# MicrocontrollerCircuit.net
KiCad netlist of a schematic drawn in EAGLE
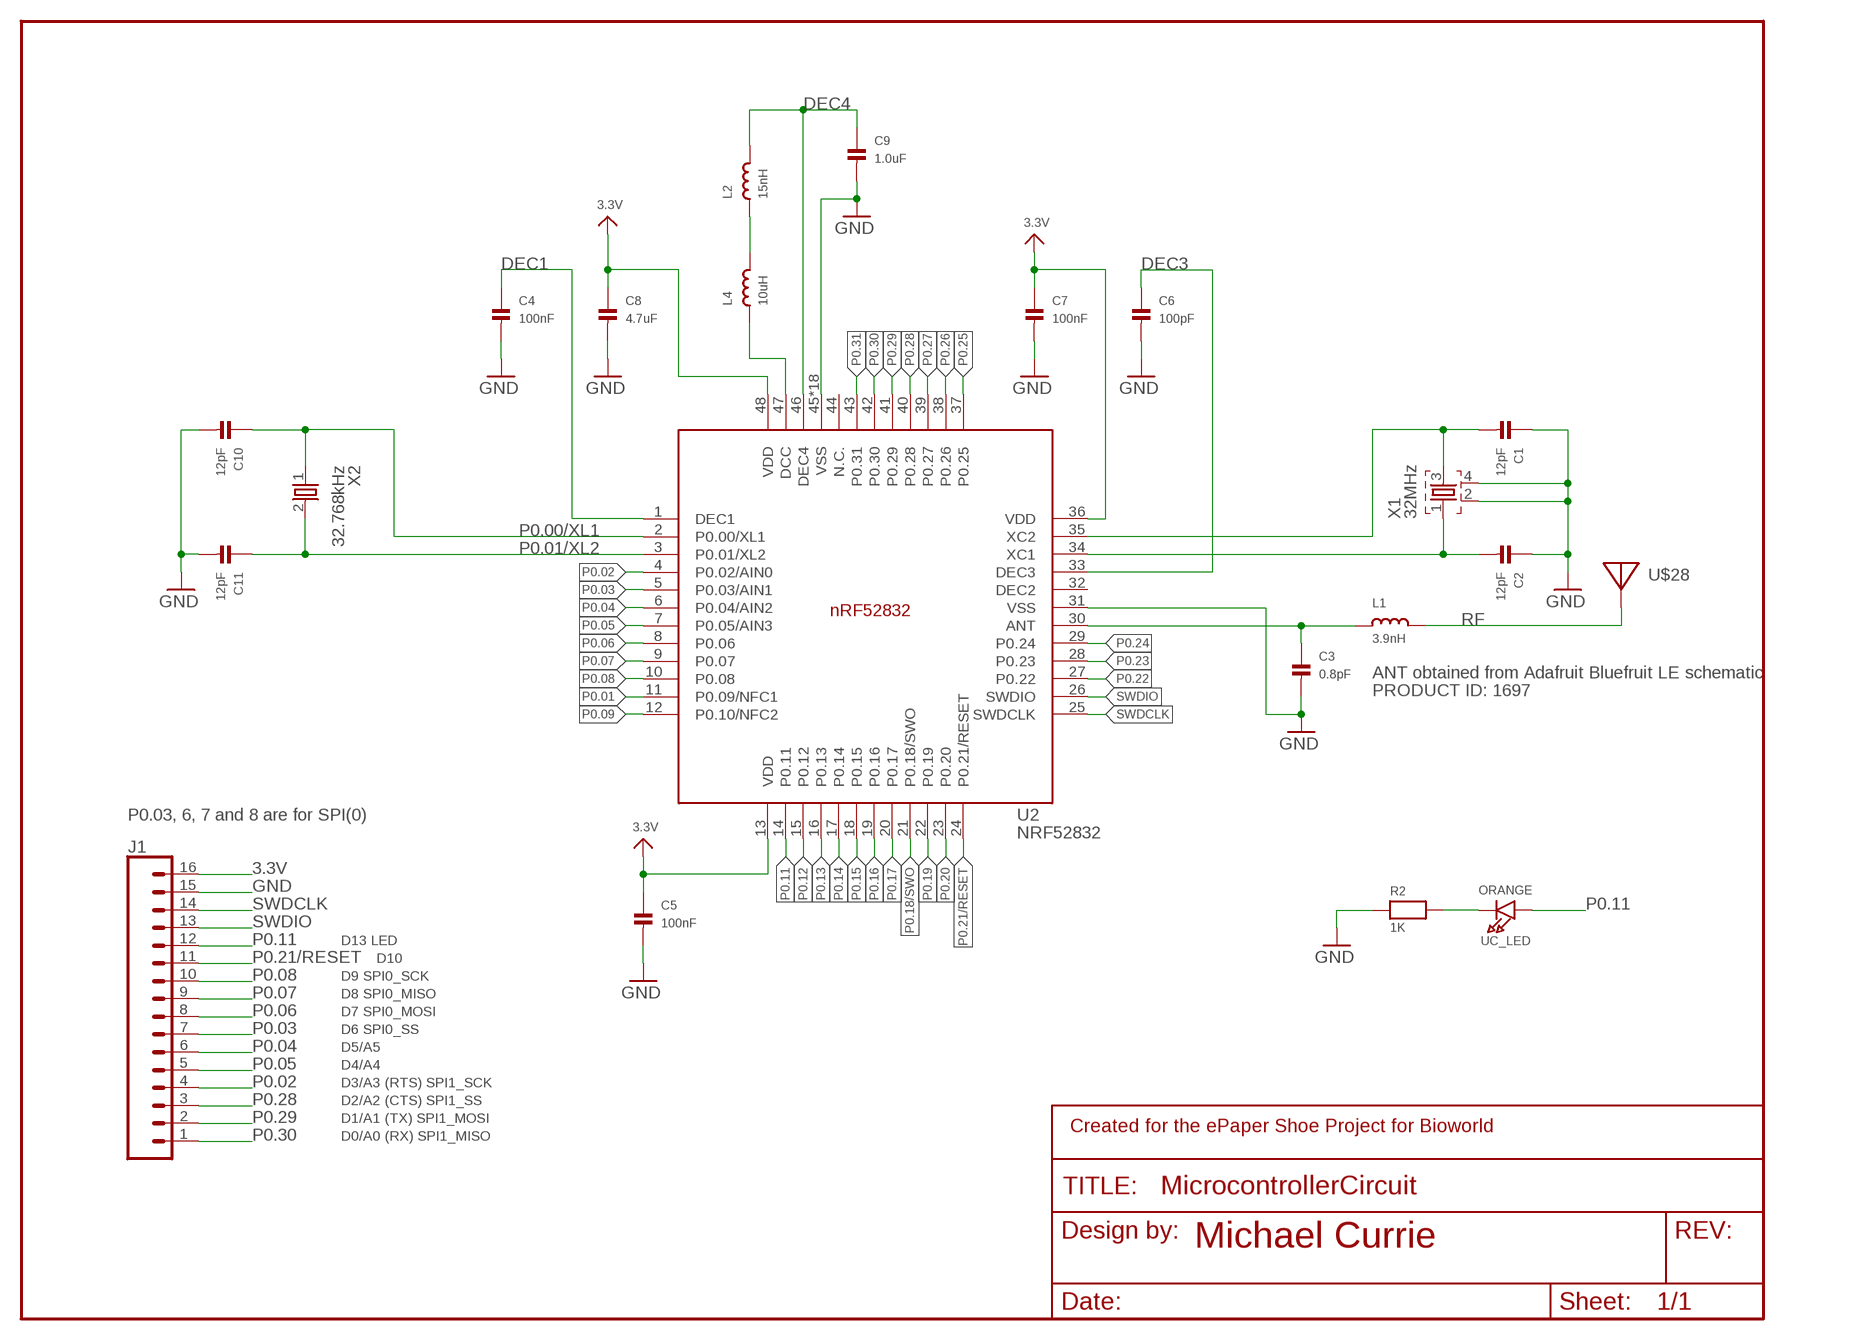
[diagram p0: schematic, sheet 1]

(export (version "E")
  (design (tool "Eeschema 10.0.6"))
  (components
    (comp (ref "C1")
      (value "12pF")
      (footprint "eagle-import:1206")
      (libsource (lib "eagle-import") (part "CAP_CERAMIC1206"))
    )
    (comp (ref "C2")
      (value "12pF")
      (footprint "eagle-import:1206")
      (libsource (lib "eagle-import") (part "CAP_CERAMIC1206"))
    )
    (comp (ref "C3")
      (value "0.8pF")
      (footprint "eagle-import:1206")
      (libsource (lib "eagle-import") (part "CAP_CERAMIC1206"))
    )
    (comp (ref "C4")
      (value "100nF")
      (footprint "eagle-import:1206")
      (libsource (lib "eagle-import") (part "CAP_CERAMIC1206"))
    )
    (comp (ref "C5")
      (value "100nF")
      (footprint "eagle-import:1206")
      (libsource (lib "eagle-import") (part "CAP_CERAMIC1206"))
    )
    (comp (ref "C6")
      (value "100pF")
      (footprint "eagle-import:1206")
      (libsource (lib "eagle-import") (part "CAP_CERAMIC1206"))
    )
    (comp (ref "C7")
      (value "100nF")
      (footprint "eagle-import:1206")
      (libsource (lib "eagle-import") (part "CAP_CERAMIC1206"))
    )
    (comp (ref "C8")
      (value "4.7uF")
      (footprint "eagle-import:1206")
      (libsource (lib "eagle-import") (part "CAP_CERAMIC1206"))
    )
    (comp (ref "C9")
      (value "1.0uF")
      (footprint "eagle-import:1206")
      (libsource (lib "eagle-import") (part "CAP_CERAMIC1206"))
    )
    (comp (ref "C10")
      (value "12pF")
      (footprint "eagle-import:1206")
      (libsource (lib "eagle-import") (part "CAP_CERAMIC1206"))
    )
    (comp (ref "C11")
      (value "12pF")
      (footprint "eagle-import:1206")
      (libsource (lib "eagle-import") (part "CAP_CERAMIC1206"))
    )
    (comp (ref "FRAME2")
      (value "FRAME-LETTER-MICHAELNO_PACKAGE")
      (footprint "eagle-import:DUMMY")
      (fields (field (name "DESIGNER") "Nobody"))
      (libsource (lib "eagle-import") (part "FRAME-LETTER-MICHAELNO_PACKAGE"))
    )
    (comp (ref "J1")
      (value "CONN_16")
      (footprint "eagle-import:1X16")
      (libsource (lib "eagle-import") (part "CONN_16"))
    )
    (comp (ref "L1")
      (value "3.9nH")
      (footprint "eagle-import:0805")
      (libsource (lib "eagle-import") (part "INDUCTOR0805"))
    )
    (comp (ref "L2")
      (value "15nH")
      (footprint "eagle-import:0805")
      (libsource (lib "eagle-import") (part "INDUCTOR0805"))
    )
    (comp (ref "L4")
      (value "10uH")
      (footprint "eagle-import:0805")
      (libsource (lib "eagle-import") (part "INDUCTOR0805"))
    )
    (comp (ref "R2")
      (value "1K")
      (footprint "eagle-import:0805")
      (libsource (lib "eagle-import") (part "RESISTOR0805"))
    )
    (comp (ref "U$28")
      (value "ANTENNA_PCBNRF8001_1.6MM")
      (footprint "eagle-import:ANT_PCB_2.4GHZ_NRF8001_1.6MM_1OZ")
      (libsource (lib "eagle-import") (part "ANTENNA_PCBNRF8001_1.6MM"))
    )
    (comp (ref "U2")
      (value "NRF52832")
      (footprint "eagle-import:QFN40P600X600X90-48_N")
      (libsource (lib "eagle-import") (part "NRF52832"))
    )
    (comp (ref "UC_LED")
      (value "ORANGE")
      (footprint "eagle-import:CHIPLED_0805_NOOUTLINE")
      (libsource (lib "eagle-import") (part "LED0805_NOOUTLINE"))
    )
    (comp (ref "X1")
      (value "32MHz")
      (footprint "eagle-import:BT-XTAL_2016_N")
      (libsource (lib "eagle-import") (part "XTAL_32MHZ"))
    )
    (comp (ref "X2")
      (value "32.768kHz")
      (footprint "eagle-import:XTAL_3215_N")
      (libsource (lib "eagle-import") (part "XTAL_32KHZ"))
    )
  )
  (nets
    (net (code "1") (name "/DEC1") (class "Default")
      (node (ref "C4") (pin "1") (pinfunction "P$1_1") (pintype "passive"))
      (node (ref "U2") (pin "1") (pinfunction "DEC1_1") (pintype "power_in"))
    )
    (net (code "2") (name "/DEC3") (class "Default")
      (node (ref "C6") (pin "1") (pinfunction "P$1_1") (pintype "passive"))
      (node (ref "U2") (pin "33") (pinfunction "DEC3_33") (pintype "bidirectional"))
    )
    (net (code "3") (name "/DEC4") (class "Default")
      (node (ref "C9") (pin "1") (pinfunction "P$1_1") (pintype "passive"))
      (node (ref "L2") (pin "2") (pinfunction "2_2") (pintype "passive"))
      (node (ref "U2") (pin "46") (pinfunction "DEC4_46") (pintype "power_in"))
    )
    (net (code "4") (name "/P0.00{slash}XL1") (class "Default")
      (node (ref "C10") (pin "1") (pinfunction "P$1_1") (pintype "passive"))
      (node (ref "U2") (pin "2") (pinfunction "P0.00/XL1_2") (pintype "bidirectional"))
      (node (ref "X2") (pin "1") (pinfunction "1_1") (pintype "passive"))
    )
    (net (code "5") (name "/P0.01{slash}XL2") (class "Default")
      (node (ref "C11") (pin "1") (pinfunction "P$1_1") (pintype "passive"))
      (node (ref "U2") (pin "3") (pinfunction "P0.01/XL2_3") (pintype "bidirectional"))
      (node (ref "X2") (pin "2") (pinfunction "2_2") (pintype "passive"))
    )
    (net (code "6") (name "/RF") (class "Default")
      (node (ref "L1") (pin "2") (pinfunction "2_2") (pintype "passive"))
      (node (ref "U$28") (pin "FEED") (pinfunction "P$1_FEED") (pintype "passive"))
    )
    (net (code "7") (name "3.3V") (class "Default")
      (node (ref "C5") (pin "1") (pinfunction "P$1_1") (pintype "passive"))
      (node (ref "C7") (pin "1") (pinfunction "P$1_1") (pintype "passive"))
      (node (ref "C8") (pin "1") (pinfunction "P$1_1") (pintype "passive"))
      (node (ref "J1") (pin "16") (pinfunction "16_16") (pintype "passive"))
      (node (ref "U2") (pin "13") (pinfunction "VDD_13") (pintype "power_in"))
      (node (ref "U2") (pin "36") (pinfunction "VDD_36") (pintype "power_in"))
      (node (ref "U2") (pin "48") (pinfunction "VDD_48") (pintype "power_in"))
    )
    (net (code "8") (name "GND") (class "Default")
      (node (ref "C1") (pin "1") (pinfunction "P$1_1") (pintype "passive"))
      (node (ref "C10") (pin "2") (pinfunction "P$2_2") (pintype "passive"))
      (node (ref "C11") (pin "2") (pinfunction "P$2_2") (pintype "passive"))
      (node (ref "C2") (pin "1") (pinfunction "P$1_1") (pintype "passive"))
      (node (ref "C3") (pin "2") (pinfunction "P$2_2") (pintype "passive"))
      (node (ref "C4") (pin "2") (pinfunction "P$2_2") (pintype "passive"))
      (node (ref "C5") (pin "2") (pinfunction "P$2_2") (pintype "passive"))
      (node (ref "C6") (pin "2") (pinfunction "P$2_2") (pintype "passive"))
      (node (ref "C7") (pin "2") (pinfunction "P$2_2") (pintype "passive"))
      (node (ref "C8") (pin "2") (pinfunction "P$2_2") (pintype "passive"))
      (node (ref "C9") (pin "2") (pinfunction "P$2_2") (pintype "passive"))
      (node (ref "J1") (pin "15") (pinfunction "15_15") (pintype "passive"))
      (node (ref "R2") (pin "1") (pinfunction "1_1") (pintype "passive"))
      (node (ref "U2") (pin "31") (pinfunction "VSS_31") (pintype "bidirectional"))
      (node (ref "U2") (pin "45") (pinfunction "VSS_45") (pintype "power_in"))
      (node (ref "U2") (pin "PAD") (pinfunction "VSS_PAD") (pintype "power_in"))
      (node (ref "U2") (pin "PAD@VIA01") (pinfunction "VSS_PAD@VIA01") (pintype "power_in"))
      (node (ref "U2") (pin "PAD@VIA02") (pinfunction "VSS_PAD@VIA02") (pintype "power_in"))
      (node (ref "U2") (pin "PAD@VIA03") (pinfunction "VSS_PAD@VIA03") (pintype "power_in"))
      (node (ref "U2") (pin "PAD@VIA04") (pinfunction "VSS_PAD@VIA04") (pintype "power_in"))
      (node (ref "U2") (pin "PAD@VIA05") (pinfunction "VSS_PAD@VIA05") (pintype "power_in"))
      (node (ref "U2") (pin "PAD@VIA06") (pinfunction "VSS_PAD@VIA06") (pintype "power_in"))
      (node (ref "U2") (pin "PAD@VIA07") (pinfunction "VSS_PAD@VIA07") (pintype "power_in"))
      (node (ref "U2") (pin "PAD@VIA08") (pinfunction "VSS_PAD@VIA08") (pintype "power_in"))
      (node (ref "U2") (pin "PAD@VIA09") (pinfunction "VSS_PAD@VIA09") (pintype "power_in"))
      (node (ref "U2") (pin "PAD@VIA10") (pinfunction "VSS_PAD@VIA10") (pintype "power_in"))
      (node (ref "U2") (pin "PAD@VIA11") (pinfunction "VSS_PAD@VIA11") (pintype "power_in"))
      (node (ref "U2") (pin "PAD@VIA12") (pinfunction "VSS_PAD@VIA12") (pintype "power_in"))
      (node (ref "U2") (pin "PAD@VIA13") (pinfunction "VSS_PAD@VIA13") (pintype "power_in"))
      (node (ref "U2") (pin "PAD@VIA14") (pinfunction "VSS_PAD@VIA14") (pintype "power_in"))
      (node (ref "U2") (pin "PAD@VIA15") (pinfunction "VSS_PAD@VIA15") (pintype "power_in"))
      (node (ref "U2") (pin "PAD@VIA16") (pinfunction "VSS_PAD@VIA16") (pintype "power_in"))
      (node (ref "X1") (pin "2") (pinfunction "2_2") (pintype "passive"))
      (node (ref "X1") (pin "4") (pinfunction "4_4") (pintype "passive"))
    )
    (net (code "9") (name "Net-(C1-P$2)") (class "Default")
      (node (ref "C1") (pin "2") (pinfunction "P$2_2") (pintype "passive"))
      (node (ref "U2") (pin "35") (pinfunction "XC2_35") (pintype "output"))
      (node (ref "X1") (pin "3") (pinfunction "3_3") (pintype "passive"))
    )
    (net (code "10") (name "Net-(C2-P$2)") (class "Default")
      (node (ref "C2") (pin "2") (pinfunction "P$2_2") (pintype "passive"))
      (node (ref "U2") (pin "34") (pinfunction "XC1_34") (pintype "input"))
      (node (ref "X1") (pin "1") (pinfunction "1_1") (pintype "passive"))
    )
    (net (code "11") (name "Net-(C3-P$1)") (class "Default")
      (node (ref "C3") (pin "1") (pinfunction "P$1_1") (pintype "passive"))
      (node (ref "L1") (pin "1") (pinfunction "1_1") (pintype "passive"))
      (node (ref "U2") (pin "30") (pinfunction "ANT_30") (pintype "bidirectional"))
    )
    (net (code "12") (name "Net-(L2-Pad1)") (class "Default")
      (node (ref "L2") (pin "1") (pinfunction "1_1") (pintype "passive"))
      (node (ref "L4") (pin "2") (pinfunction "2_2") (pintype "passive"))
    )
    (net (code "13") (name "Net-(R2-Pad2)") (class "Default")
      (node (ref "R2") (pin "2") (pinfunction "2_2") (pintype "passive"))
      (node (ref "UC_LED") (pin "C") (pinfunction "C_C") (pintype "passive"))
    )
    (net (code "14") (name "Net-(U2-DCC)") (class "Default")
      (node (ref "L4") (pin "1") (pinfunction "1_1") (pintype "passive"))
      (node (ref "U2") (pin "47") (pinfunction "DCC_47") (pintype "output"))
    )
    (net (code "15") (name "P0.01") (class "Default")
      (node (ref "U2") (pin "11") (pinfunction "P0.09/NFC1_11") (pintype "bidirectional"))
    )
    (net (code "16") (name "P0.02") (class "Default")
      (node (ref "J1") (pin "4") (pinfunction "4_4") (pintype "passive"))
      (node (ref "U2") (pin "4") (pinfunction "P0.02/AIN0_4") (pintype "bidirectional"))
    )
    (net (code "17") (name "P0.03") (class "Default")
      (node (ref "J1") (pin "7") (pinfunction "7_7") (pintype "passive"))
      (node (ref "U2") (pin "5") (pinfunction "P0.03/AIN1_5") (pintype "bidirectional"))
    )
    (net (code "18") (name "P0.04") (class "Default")
      (node (ref "J1") (pin "6") (pinfunction "6_6") (pintype "passive"))
      (node (ref "U2") (pin "6") (pinfunction "P0.04/AIN2_6") (pintype "bidirectional"))
    )
    (net (code "19") (name "P0.05") (class "Default")
      (node (ref "J1") (pin "5") (pinfunction "5_5") (pintype "passive"))
      (node (ref "U2") (pin "7") (pinfunction "P0.05/AIN3_7") (pintype "bidirectional"))
    )
    (net (code "20") (name "P0.06") (class "Default")
      (node (ref "J1") (pin "8") (pinfunction "8_8") (pintype "passive"))
      (node (ref "U2") (pin "8") (pinfunction "P0.06_8") (pintype "bidirectional"))
    )
    (net (code "21") (name "P0.07") (class "Default")
      (node (ref "J1") (pin "9") (pinfunction "9_9") (pintype "passive"))
      (node (ref "U2") (pin "9") (pinfunction "P0.07_9") (pintype "bidirectional"))
    )
    (net (code "22") (name "P0.08") (class "Default")
      (node (ref "J1") (pin "10") (pinfunction "10_10") (pintype "passive"))
      (node (ref "U2") (pin "10") (pinfunction "P0.08_10") (pintype "bidirectional"))
    )
    (net (code "23") (name "P0.09") (class "Default")
      (node (ref "U2") (pin "12") (pinfunction "P0.10/NFC2_12") (pintype "bidirectional"))
    )
    (net (code "24") (name "P0.11") (class "Default")
      (node (ref "J1") (pin "12") (pinfunction "12_12") (pintype "passive"))
      (node (ref "U2") (pin "14") (pinfunction "P0.11_14") (pintype "bidirectional"))
      (node (ref "UC_LED") (pin "A") (pinfunction "A_A") (pintype "passive"))
    )
    (net (code "25") (name "P0.12") (class "Default")
      (node (ref "U2") (pin "15") (pinfunction "P0.12_15") (pintype "bidirectional"))
    )
    (net (code "26") (name "P0.13") (class "Default")
      (node (ref "U2") (pin "16") (pinfunction "P0.13_16") (pintype "bidirectional"))
    )
    (net (code "27") (name "P0.14") (class "Default")
      (node (ref "U2") (pin "17") (pinfunction "P0.14_17") (pintype "bidirectional"))
    )
    (net (code "28") (name "P0.15") (class "Default")
      (node (ref "U2") (pin "18") (pinfunction "P0.15_18") (pintype "bidirectional"))
    )
    (net (code "29") (name "P0.16") (class "Default")
      (node (ref "U2") (pin "19") (pinfunction "P0.16_19") (pintype "bidirectional"))
    )
    (net (code "30") (name "P0.17") (class "Default")
      (node (ref "U2") (pin "20") (pinfunction "P0.17_20") (pintype "bidirectional"))
    )
    (net (code "31") (name "P0.18{slash}SWO") (class "Default")
      (node (ref "U2") (pin "21") (pinfunction "P0.18/SWO_21") (pintype "bidirectional"))
    )
    (net (code "32") (name "P0.19") (class "Default")
      (node (ref "U2") (pin "22") (pinfunction "P0.19_22") (pintype "bidirectional"))
    )
    (net (code "33") (name "P0.20") (class "Default")
      (node (ref "U2") (pin "23") (pinfunction "P0.20_23") (pintype "bidirectional"))
    )
    (net (code "34") (name "P0.21{slash}RESET") (class "Default")
      (node (ref "J1") (pin "11") (pinfunction "11_11") (pintype "passive"))
      (node (ref "U2") (pin "24") (pinfunction "P0.21/RESET_24") (pintype "bidirectional"))
    )
    (net (code "35") (name "P0.22") (class "Default")
      (node (ref "U2") (pin "27") (pinfunction "P0.22_27") (pintype "bidirectional"))
    )
    (net (code "36") (name "P0.23") (class "Default")
      (node (ref "U2") (pin "28") (pinfunction "P0.23_28") (pintype "bidirectional"))
    )
    (net (code "37") (name "P0.24") (class "Default")
      (node (ref "U2") (pin "29") (pinfunction "P0.24_29") (pintype "bidirectional"))
    )
    (net (code "38") (name "P0.25") (class "Default")
      (node (ref "U2") (pin "37") (pinfunction "P0.25_37") (pintype "bidirectional"))
    )
    (net (code "39") (name "P0.26") (class "Default")
      (node (ref "U2") (pin "38") (pinfunction "P0.26_38") (pintype "bidirectional"))
    )
    (net (code "40") (name "P0.27") (class "Default")
      (node (ref "U2") (pin "39") (pinfunction "P0.27_39") (pintype "bidirectional"))
    )
    (net (code "41") (name "P0.28") (class "Default")
      (node (ref "J1") (pin "3") (pinfunction "3_3") (pintype "passive"))
      (node (ref "U2") (pin "40") (pinfunction "P0.28_40") (pintype "bidirectional"))
    )
    (net (code "42") (name "P0.29") (class "Default")
      (node (ref "J1") (pin "2") (pinfunction "2_2") (pintype "passive"))
      (node (ref "U2") (pin "41") (pinfunction "P0.29_41") (pintype "bidirectional"))
    )
    (net (code "43") (name "P0.30") (class "Default")
      (node (ref "J1") (pin "1") (pinfunction "1_1") (pintype "passive"))
      (node (ref "U2") (pin "42") (pinfunction "P0.30_42") (pintype "bidirectional"))
    )
    (net (code "44") (name "P0.31") (class "Default")
      (node (ref "U2") (pin "43") (pinfunction "P0.31_43") (pintype "bidirectional"))
    )
    (net (code "45") (name "SWDCLK") (class "Default")
      (node (ref "J1") (pin "14") (pinfunction "14_14") (pintype "passive"))
      (node (ref "U2") (pin "25") (pinfunction "SWDCLK_25") (pintype "input"))
    )
    (net (code "46") (name "SWDIO") (class "Default")
      (node (ref "J1") (pin "13") (pinfunction "13_13") (pintype "passive"))
      (node (ref "U2") (pin "26") (pinfunction "SWDIO_26") (pintype "bidirectional"))
    )
    (net (code "47") (name "unconnected-(U2-DEC2-Pad32)") (class "Default")
      (node (ref "U2") (pin "32") (pinfunction "DEC2_32") (pintype "bidirectional"))
    )
    (net (code "48") (name "unconnected-(U2-N.C.-Pad44)") (class "Default")
      (node (ref "U2") (pin "44") (pinfunction "N.C._44") (pintype "no_connect"))
    )
  )
)
